# DB_MotherBoardConnectors.net
KiCad netlist of a schematic drawn in Altium Designer
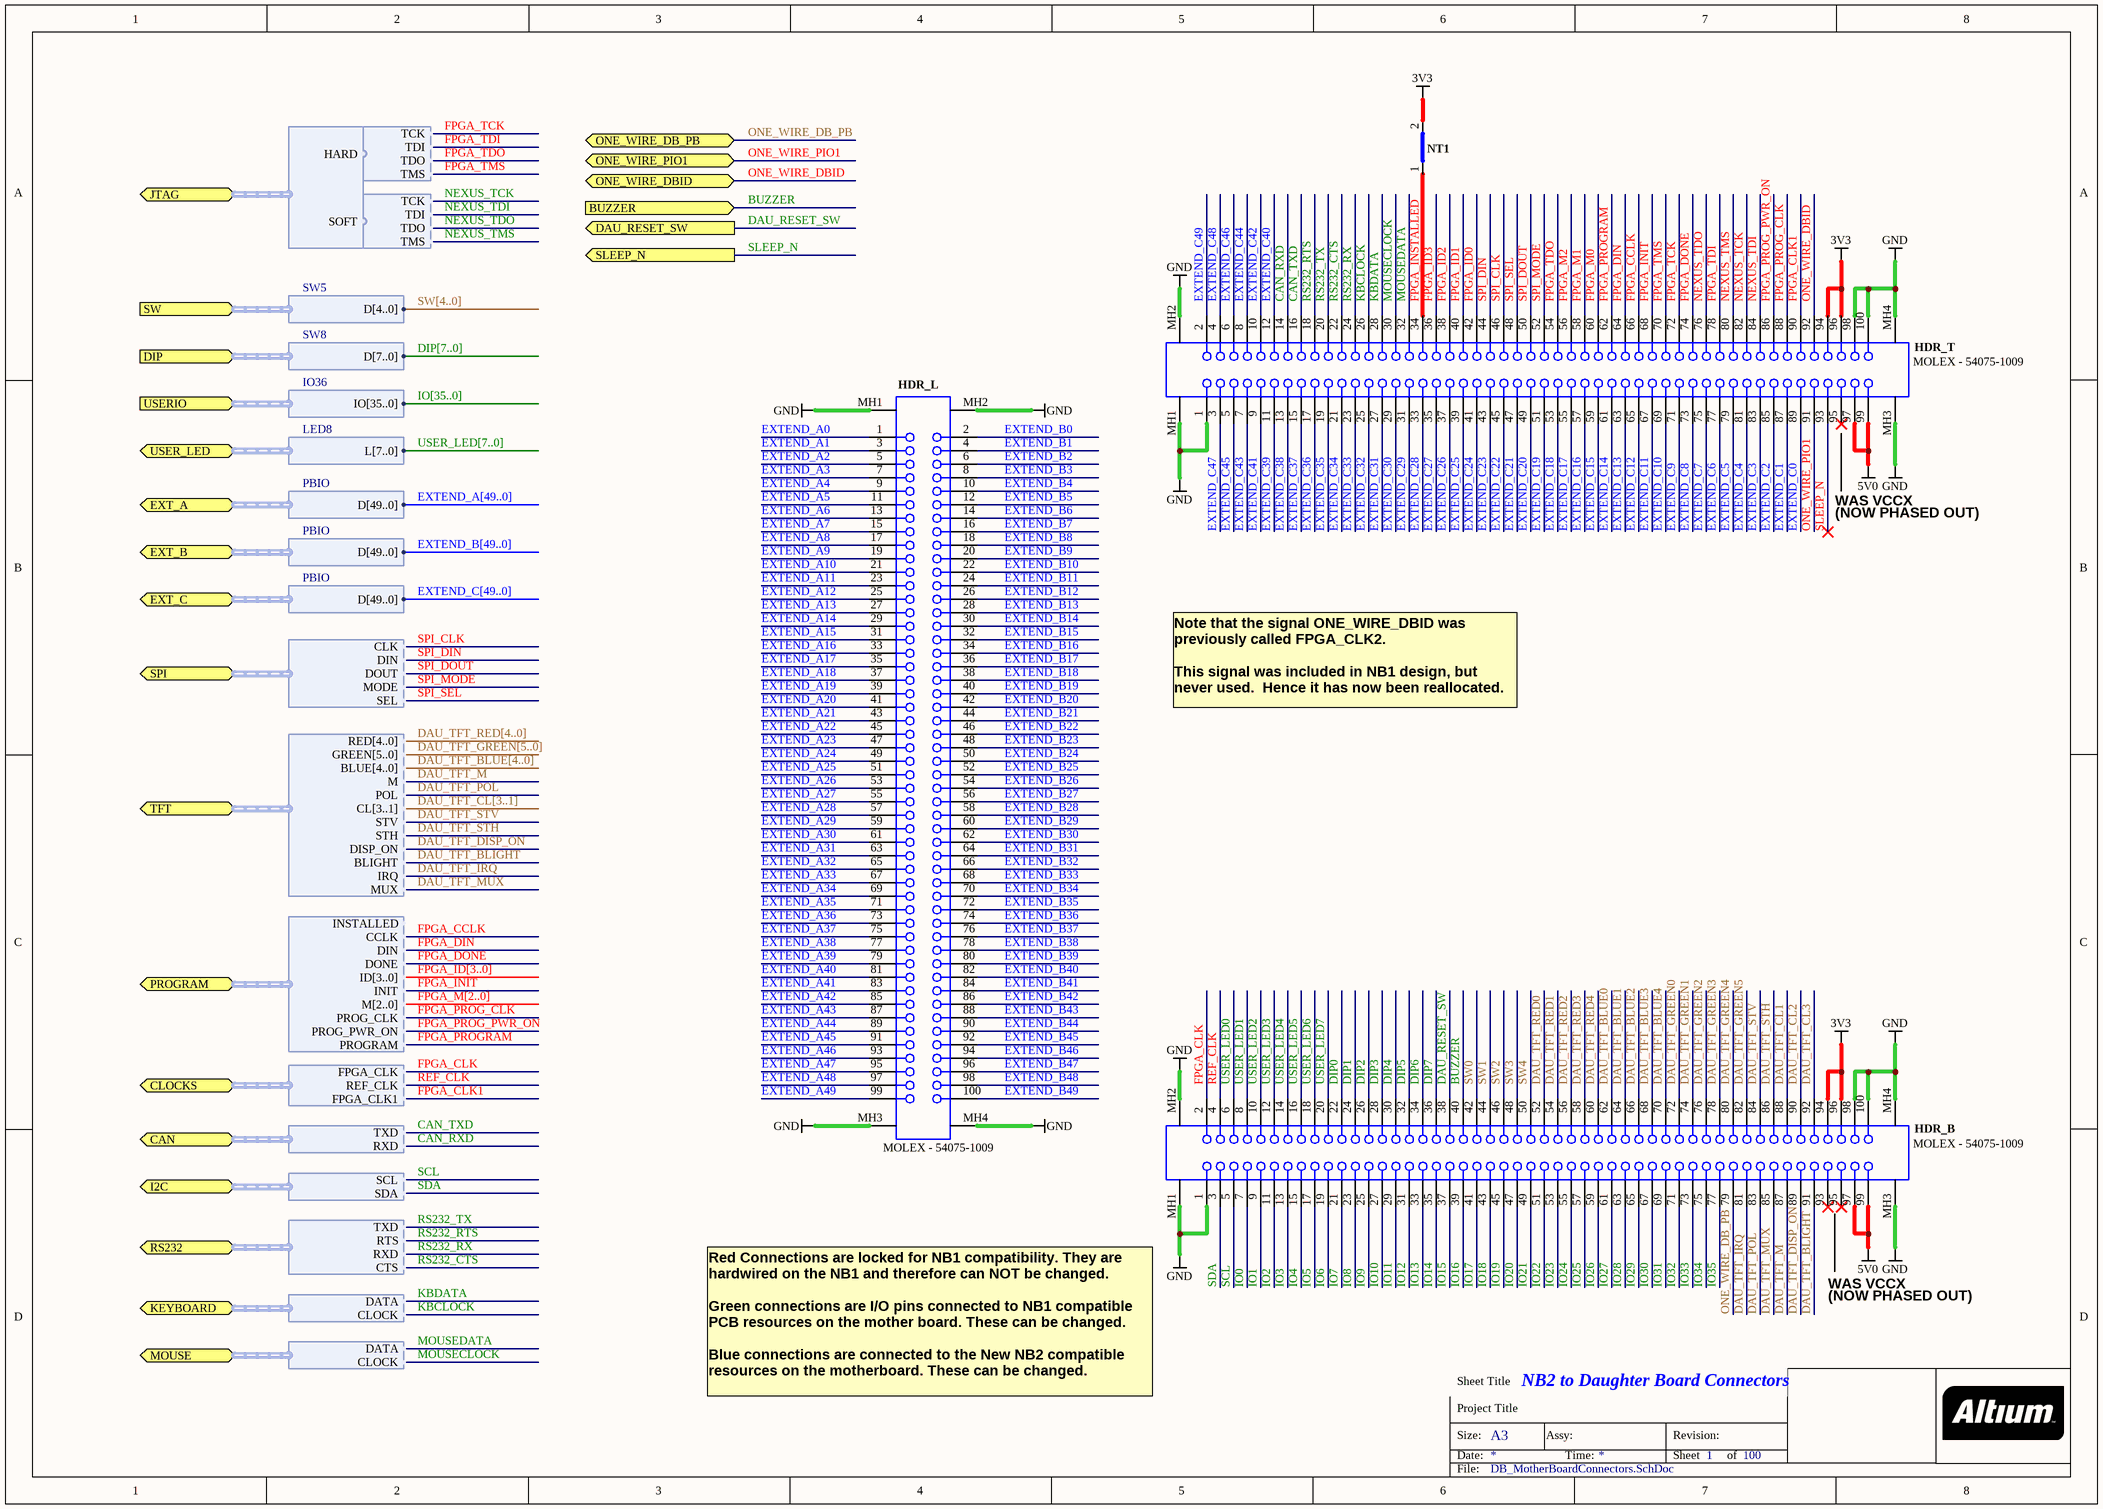
[diagram p0: DB_MotherBoardConnectors.SchDoc]

(export (version "E")
  (design (tool "Eeschema 10.0.6"))
  (components
    (comp (ref "HDR_B")
      (value "MOLEX - 54075-1009")
      (footprint "54075")
      (description "Connector, Molex Docking Station 100 Pin Male 54075")
      (libsource (lib "AltiumDesignLibrary") (part "CON-DOCKSTAT-100-M-STR"))
    )
    (comp (ref "HDR_L")
      (value "MOLEX - 54075-1009")
      (footprint "54075")
      (description "Connector, Molex Docking Station 100 Pin Male 54075")
      (libsource (lib "AltiumDesignLibrary") (part "CON-DOCKSTAT-100-M-STR"))
    )
    (comp (ref "HDR_T")
      (value "MOLEX - 54075-1009")
      (footprint "54075")
      (description "Connector, Molex Docking Station 100 Pin Male 54075")
      (libsource (lib "AltiumDesignLibrary") (part "CON-DOCKSTAT-100-M-STR"))
    )
    (comp (ref "NT1")
      (value "Net Tie SMT2")
      (footprint "NETTIE-SMT2-8X8")
      (description "Net-Tie, Surface Mount, 2 x 0.4mm x 0.2mm SMT Pads - For 0.2mm Track")
      (libsource (lib "AltiumDesignLibrary") (part "NETTIE-SMT2"))
    )
  )
  (nets
    (net (code "16") (name "/BUZZER") (class "Default")
      (node (ref "HDR_B") (pin "40") (pinfunction "40_40") (pintype "passive"))
    )
    (net (code "17") (name "/CAN_RXD") (class "Default")
      (node (ref "HDR_T") (pin "14") (pinfunction "14_14") (pintype "passive"))
    )
    (net (code "18") (name "/CAN_TXD") (class "Default")
      (node (ref "HDR_T") (pin "16") (pinfunction "16_16") (pintype "passive"))
    )
    (net (code "19") (name "/DAU_RESET_SW") (class "Default")
      (node (ref "HDR_B") (pin "38") (pinfunction "38_38") (pintype "passive"))
    )
    (net (code "20") (name "/DAU_TFT_BLIGHT") (class "Default")
      (node (ref "HDR_B") (pin "91") (pinfunction "91_91") (pintype "passive"))
    )
    (net (code "21") (name "/DAU_TFT_BLUE0") (class "Default")
      (node (ref "HDR_B") (pin "62") (pinfunction "62_62") (pintype "passive"))
    )
    (net (code "22") (name "/DAU_TFT_BLUE1") (class "Default")
      (node (ref "HDR_B") (pin "64") (pinfunction "64_64") (pintype "passive"))
    )
    (net (code "23") (name "/DAU_TFT_BLUE2") (class "Default")
      (node (ref "HDR_B") (pin "66") (pinfunction "66_66") (pintype "passive"))
    )
    (net (code "24") (name "/DAU_TFT_BLUE3") (class "Default")
      (node (ref "HDR_B") (pin "68") (pinfunction "68_68") (pintype "passive"))
    )
    (net (code "25") (name "/DAU_TFT_BLUE4") (class "Default")
      (node (ref "HDR_B") (pin "70") (pinfunction "70_70") (pintype "passive"))
    )
    (net (code "27") (name "/DAU_TFT_CL1") (class "Default")
      (node (ref "HDR_B") (pin "88") (pinfunction "88_88") (pintype "passive"))
    )
    (net (code "28") (name "/DAU_TFT_CL2") (class "Default")
      (node (ref "HDR_B") (pin "90") (pinfunction "90_90") (pintype "passive"))
    )
    (net (code "29") (name "/DAU_TFT_CL3") (class "Default")
      (node (ref "HDR_B") (pin "92") (pinfunction "92_92") (pintype "passive"))
    )
    (net (code "30") (name "/DAU_TFT_DISP_ON") (class "Default")
      (node (ref "HDR_B") (pin "89") (pinfunction "89_89") (pintype "passive"))
    )
    (net (code "31") (name "/DAU_TFT_GREEN0") (class "Default")
      (node (ref "HDR_B") (pin "72") (pinfunction "72_72") (pintype "passive"))
    )
    (net (code "32") (name "/DAU_TFT_GREEN1") (class "Default")
      (node (ref "HDR_B") (pin "74") (pinfunction "74_74") (pintype "passive"))
    )
    (net (code "33") (name "/DAU_TFT_GREEN2") (class "Default")
      (node (ref "HDR_B") (pin "76") (pinfunction "76_76") (pintype "passive"))
    )
    (net (code "34") (name "/DAU_TFT_GREEN3") (class "Default")
      (node (ref "HDR_B") (pin "78") (pinfunction "78_78") (pintype "passive"))
    )
    (net (code "35") (name "/DAU_TFT_GREEN4") (class "Default")
      (node (ref "HDR_B") (pin "80") (pinfunction "80_80") (pintype "passive"))
    )
    (net (code "36") (name "/DAU_TFT_GREEN5") (class "Default")
      (node (ref "HDR_B") (pin "82") (pinfunction "82_82") (pintype "passive"))
    )
    (net (code "38") (name "/DAU_TFT_IRQ") (class "Default")
      (node (ref "HDR_B") (pin "81") (pinfunction "81_81") (pintype "passive"))
    )
    (net (code "39") (name "/DAU_TFT_M") (class "Default")
      (node (ref "HDR_B") (pin "87") (pinfunction "87_87") (pintype "passive"))
    )
    (net (code "40") (name "/DAU_TFT_MUX") (class "Default")
      (node (ref "HDR_B") (pin "85") (pinfunction "85_85") (pintype "passive"))
    )
    (net (code "41") (name "/DAU_TFT_POL") (class "Default")
      (node (ref "HDR_B") (pin "83") (pinfunction "83_83") (pintype "passive"))
    )
    (net (code "42") (name "/DAU_TFT_RED0") (class "Default")
      (node (ref "HDR_B") (pin "52") (pinfunction "52_52") (pintype "passive"))
    )
    (net (code "43") (name "/DAU_TFT_RED1") (class "Default")
      (node (ref "HDR_B") (pin "54") (pinfunction "54_54") (pintype "passive"))
    )
    (net (code "44") (name "/DAU_TFT_RED2") (class "Default")
      (node (ref "HDR_B") (pin "56") (pinfunction "56_56") (pintype "passive"))
    )
    (net (code "45") (name "/DAU_TFT_RED3") (class "Default")
      (node (ref "HDR_B") (pin "58") (pinfunction "58_58") (pintype "passive"))
    )
    (net (code "46") (name "/DAU_TFT_RED4") (class "Default")
      (node (ref "HDR_B") (pin "60") (pinfunction "60_60") (pintype "passive"))
    )
    (net (code "48") (name "/DAU_TFT_STH") (class "Default")
      (node (ref "HDR_B") (pin "86") (pinfunction "86_86") (pintype "passive"))
    )
    (net (code "49") (name "/DAU_TFT_STV") (class "Default")
      (node (ref "HDR_B") (pin "84") (pinfunction "84_84") (pintype "passive"))
    )
    (net (code "50") (name "/DIP0") (class "Default")
      (node (ref "HDR_B") (pin "22") (pinfunction "22_22") (pintype "passive"))
    )
    (net (code "51") (name "/DIP1") (class "Default")
      (node (ref "HDR_B") (pin "24") (pinfunction "24_24") (pintype "passive"))
    )
    (net (code "52") (name "/DIP2") (class "Default")
      (node (ref "HDR_B") (pin "26") (pinfunction "26_26") (pintype "passive"))
    )
    (net (code "53") (name "/DIP3") (class "Default")
      (node (ref "HDR_B") (pin "28") (pinfunction "28_28") (pintype "passive"))
    )
    (net (code "54") (name "/DIP4") (class "Default")
      (node (ref "HDR_B") (pin "30") (pinfunction "30_30") (pintype "passive"))
    )
    (net (code "55") (name "/DIP5") (class "Default")
      (node (ref "HDR_B") (pin "32") (pinfunction "32_32") (pintype "passive"))
    )
    (net (code "56") (name "/DIP6") (class "Default")
      (node (ref "HDR_B") (pin "34") (pinfunction "34_34") (pintype "passive"))
    )
    (net (code "57") (name "/DIP7") (class "Default")
      (node (ref "HDR_B") (pin "36") (pinfunction "36_36") (pintype "passive"))
    )
    (net (code "59") (name "/EXTEND_A0") (class "Default")
      (node (ref "HDR_L") (pin "1") (pinfunction "1_1") (pintype "passive"))
    )
    (net (code "60") (name "/EXTEND_A1") (class "Default")
      (node (ref "HDR_L") (pin "3") (pinfunction "3_3") (pintype "passive"))
    )
    (net (code "61") (name "/EXTEND_A2") (class "Default")
      (node (ref "HDR_L") (pin "5") (pinfunction "5_5") (pintype "passive"))
    )
    (net (code "62") (name "/EXTEND_A3") (class "Default")
      (node (ref "HDR_L") (pin "7") (pinfunction "7_7") (pintype "passive"))
    )
    (net (code "63") (name "/EXTEND_A4") (class "Default")
      (node (ref "HDR_L") (pin "9") (pinfunction "9_9") (pintype "passive"))
    )
    (net (code "64") (name "/EXTEND_A5") (class "Default")
      (node (ref "HDR_L") (pin "11") (pinfunction "11_11") (pintype "passive"))
    )
    (net (code "65") (name "/EXTEND_A6") (class "Default")
      (node (ref "HDR_L") (pin "13") (pinfunction "13_13") (pintype "passive"))
    )
    (net (code "66") (name "/EXTEND_A7") (class "Default")
      (node (ref "HDR_L") (pin "15") (pinfunction "15_15") (pintype "passive"))
    )
    (net (code "67") (name "/EXTEND_A8") (class "Default")
      (node (ref "HDR_L") (pin "17") (pinfunction "17_17") (pintype "passive"))
    )
    (net (code "68") (name "/EXTEND_A9") (class "Default")
      (node (ref "HDR_L") (pin "19") (pinfunction "19_19") (pintype "passive"))
    )
    (net (code "69") (name "/EXTEND_A10") (class "Default")
      (node (ref "HDR_L") (pin "21") (pinfunction "21_21") (pintype "passive"))
    )
    (net (code "70") (name "/EXTEND_A11") (class "Default")
      (node (ref "HDR_L") (pin "23") (pinfunction "23_23") (pintype "passive"))
    )
    (net (code "71") (name "/EXTEND_A12") (class "Default")
      (node (ref "HDR_L") (pin "25") (pinfunction "25_25") (pintype "passive"))
    )
    (net (code "72") (name "/EXTEND_A13") (class "Default")
      (node (ref "HDR_L") (pin "27") (pinfunction "27_27") (pintype "passive"))
    )
    (net (code "73") (name "/EXTEND_A14") (class "Default")
      (node (ref "HDR_L") (pin "29") (pinfunction "29_29") (pintype "passive"))
    )
    (net (code "74") (name "/EXTEND_A15") (class "Default")
      (node (ref "HDR_L") (pin "31") (pinfunction "31_31") (pintype "passive"))
    )
    (net (code "75") (name "/EXTEND_A16") (class "Default")
      (node (ref "HDR_L") (pin "33") (pinfunction "33_33") (pintype "passive"))
    )
    (net (code "76") (name "/EXTEND_A17") (class "Default")
      (node (ref "HDR_L") (pin "35") (pinfunction "35_35") (pintype "passive"))
    )
    (net (code "77") (name "/EXTEND_A18") (class "Default")
      (node (ref "HDR_L") (pin "37") (pinfunction "37_37") (pintype "passive"))
    )
    (net (code "78") (name "/EXTEND_A19") (class "Default")
      (node (ref "HDR_L") (pin "39") (pinfunction "39_39") (pintype "passive"))
    )
    (net (code "79") (name "/EXTEND_A20") (class "Default")
      (node (ref "HDR_L") (pin "41") (pinfunction "41_41") (pintype "passive"))
    )
    (net (code "80") (name "/EXTEND_A21") (class "Default")
      (node (ref "HDR_L") (pin "43") (pinfunction "43_43") (pintype "passive"))
    )
    (net (code "81") (name "/EXTEND_A22") (class "Default")
      (node (ref "HDR_L") (pin "45") (pinfunction "45_45") (pintype "passive"))
    )
    (net (code "82") (name "/EXTEND_A23") (class "Default")
      (node (ref "HDR_L") (pin "47") (pinfunction "47_47") (pintype "passive"))
    )
    (net (code "83") (name "/EXTEND_A24") (class "Default")
      (node (ref "HDR_L") (pin "49") (pinfunction "49_49") (pintype "passive"))
    )
    (net (code "84") (name "/EXTEND_A25") (class "Default")
      (node (ref "HDR_L") (pin "51") (pinfunction "51_51") (pintype "passive"))
    )
    (net (code "85") (name "/EXTEND_A26") (class "Default")
      (node (ref "HDR_L") (pin "53") (pinfunction "53_53") (pintype "passive"))
    )
    (net (code "86") (name "/EXTEND_A27") (class "Default")
      (node (ref "HDR_L") (pin "55") (pinfunction "55_55") (pintype "passive"))
    )
    (net (code "87") (name "/EXTEND_A28") (class "Default")
      (node (ref "HDR_L") (pin "57") (pinfunction "57_57") (pintype "passive"))
    )
    (net (code "88") (name "/EXTEND_A29") (class "Default")
      (node (ref "HDR_L") (pin "59") (pinfunction "59_59") (pintype "passive"))
    )
    (net (code "89") (name "/EXTEND_A30") (class "Default")
      (node (ref "HDR_L") (pin "61") (pinfunction "61_61") (pintype "passive"))
    )
    (net (code "90") (name "/EXTEND_A31") (class "Default")
      (node (ref "HDR_L") (pin "63") (pinfunction "63_63") (pintype "passive"))
    )
    (net (code "91") (name "/EXTEND_A32") (class "Default")
      (node (ref "HDR_L") (pin "65") (pinfunction "65_65") (pintype "passive"))
    )
    (net (code "92") (name "/EXTEND_A33") (class "Default")
      (node (ref "HDR_L") (pin "67") (pinfunction "67_67") (pintype "passive"))
    )
    (net (code "93") (name "/EXTEND_A34") (class "Default")
      (node (ref "HDR_L") (pin "69") (pinfunction "69_69") (pintype "passive"))
    )
    (net (code "94") (name "/EXTEND_A35") (class "Default")
      (node (ref "HDR_L") (pin "71") (pinfunction "71_71") (pintype "passive"))
    )
    (net (code "95") (name "/EXTEND_A36") (class "Default")
      (node (ref "HDR_L") (pin "73") (pinfunction "73_73") (pintype "passive"))
    )
    (net (code "96") (name "/EXTEND_A37") (class "Default")
      (node (ref "HDR_L") (pin "75") (pinfunction "75_75") (pintype "passive"))
    )
    (net (code "97") (name "/EXTEND_A38") (class "Default")
      (node (ref "HDR_L") (pin "77") (pinfunction "77_77") (pintype "passive"))
    )
    (net (code "98") (name "/EXTEND_A39") (class "Default")
      (node (ref "HDR_L") (pin "79") (pinfunction "79_79") (pintype "passive"))
    )
    (net (code "99") (name "/EXTEND_A40") (class "Default")
      (node (ref "HDR_L") (pin "81") (pinfunction "81_81") (pintype "passive"))
    )
    (net (code "100") (name "/EXTEND_A41") (class "Default")
      (node (ref "HDR_L") (pin "83") (pinfunction "83_83") (pintype "passive"))
    )
    (net (code "101") (name "/EXTEND_A42") (class "Default")
      (node (ref "HDR_L") (pin "85") (pinfunction "85_85") (pintype "passive"))
    )
    (net (code "102") (name "/EXTEND_A43") (class "Default")
      (node (ref "HDR_L") (pin "87") (pinfunction "87_87") (pintype "passive"))
    )
    (net (code "103") (name "/EXTEND_A44") (class "Default")
      (node (ref "HDR_L") (pin "89") (pinfunction "89_89") (pintype "passive"))
    )
    (net (code "104") (name "/EXTEND_A45") (class "Default")
      (node (ref "HDR_L") (pin "91") (pinfunction "91_91") (pintype "passive"))
    )
    (net (code "105") (name "/EXTEND_A46") (class "Default")
      (node (ref "HDR_L") (pin "93") (pinfunction "93_93") (pintype "passive"))
    )
    (net (code "106") (name "/EXTEND_A47") (class "Default")
      (node (ref "HDR_L") (pin "95") (pinfunction "95_95") (pintype "passive"))
    )
    (net (code "107") (name "/EXTEND_A48") (class "Default")
      (node (ref "HDR_L") (pin "97") (pinfunction "97_97") (pintype "passive"))
    )
    (net (code "108") (name "/EXTEND_A49") (class "Default")
      (node (ref "HDR_L") (pin "99") (pinfunction "99_99") (pintype "passive"))
    )
    (net (code "110") (name "/EXTEND_B0") (class "Default")
      (node (ref "HDR_L") (pin "2") (pinfunction "2_2") (pintype "passive"))
    )
    (net (code "111") (name "/EXTEND_B1") (class "Default")
      (node (ref "HDR_L") (pin "4") (pinfunction "4_4") (pintype "passive"))
    )
    (net (code "112") (name "/EXTEND_B2") (class "Default")
      (node (ref "HDR_L") (pin "6") (pinfunction "6_6") (pintype "passive"))
    )
    (net (code "113") (name "/EXTEND_B3") (class "Default")
      (node (ref "HDR_L") (pin "8") (pinfunction "8_8") (pintype "passive"))
    )
    (net (code "114") (name "/EXTEND_B4") (class "Default")
      (node (ref "HDR_L") (pin "10") (pinfunction "10_10") (pintype "passive"))
    )
    (net (code "115") (name "/EXTEND_B5") (class "Default")
      (node (ref "HDR_L") (pin "12") (pinfunction "12_12") (pintype "passive"))
    )
    (net (code "116") (name "/EXTEND_B6") (class "Default")
      (node (ref "HDR_L") (pin "14") (pinfunction "14_14") (pintype "passive"))
    )
    (net (code "117") (name "/EXTEND_B7") (class "Default")
      (node (ref "HDR_L") (pin "16") (pinfunction "16_16") (pintype "passive"))
    )
    (net (code "118") (name "/EXTEND_B8") (class "Default")
      (node (ref "HDR_L") (pin "18") (pinfunction "18_18") (pintype "passive"))
    )
    (net (code "119") (name "/EXTEND_B9") (class "Default")
      (node (ref "HDR_L") (pin "20") (pinfunction "20_20") (pintype "passive"))
    )
    (net (code "120") (name "/EXTEND_B10") (class "Default")
      (node (ref "HDR_L") (pin "22") (pinfunction "22_22") (pintype "passive"))
    )
    (net (code "121") (name "/EXTEND_B11") (class "Default")
      (node (ref "HDR_L") (pin "24") (pinfunction "24_24") (pintype "passive"))
    )
    (net (code "122") (name "/EXTEND_B12") (class "Default")
      (node (ref "HDR_L") (pin "26") (pinfunction "26_26") (pintype "passive"))
    )
    (net (code "123") (name "/EXTEND_B13") (class "Default")
      (node (ref "HDR_L") (pin "28") (pinfunction "28_28") (pintype "passive"))
    )
    (net (code "124") (name "/EXTEND_B14") (class "Default")
      (node (ref "HDR_L") (pin "30") (pinfunction "30_30") (pintype "passive"))
    )
    (net (code "125") (name "/EXTEND_B15") (class "Default")
      (node (ref "HDR_L") (pin "32") (pinfunction "32_32") (pintype "passive"))
    )
    (net (code "126") (name "/EXTEND_B16") (class "Default")
      (node (ref "HDR_L") (pin "34") (pinfunction "34_34") (pintype "passive"))
    )
    (net (code "127") (name "/EXTEND_B17") (class "Default")
      (node (ref "HDR_L") (pin "36") (pinfunction "36_36") (pintype "passive"))
    )
    (net (code "128") (name "/EXTEND_B18") (class "Default")
      (node (ref "HDR_L") (pin "38") (pinfunction "38_38") (pintype "passive"))
    )
    (net (code "129") (name "/EXTEND_B19") (class "Default")
      (node (ref "HDR_L") (pin "40") (pinfunction "40_40") (pintype "passive"))
    )
    (net (code "130") (name "/EXTEND_B20") (class "Default")
      (node (ref "HDR_L") (pin "42") (pinfunction "42_42") (pintype "passive"))
    )
    (net (code "131") (name "/EXTEND_B21") (class "Default")
      (node (ref "HDR_L") (pin "44") (pinfunction "44_44") (pintype "passive"))
    )
    (net (code "132") (name "/EXTEND_B22") (class "Default")
      (node (ref "HDR_L") (pin "46") (pinfunction "46_46") (pintype "passive"))
    )
    (net (code "133") (name "/EXTEND_B23") (class "Default")
      (node (ref "HDR_L") (pin "48") (pinfunction "48_48") (pintype "passive"))
    )
    (net (code "134") (name "/EXTEND_B24") (class "Default")
      (node (ref "HDR_L") (pin "50") (pinfunction "50_50") (pintype "passive"))
    )
    (net (code "135") (name "/EXTEND_B25") (class "Default")
      (node (ref "HDR_L") (pin "52") (pinfunction "52_52") (pintype "passive"))
    )
    (net (code "136") (name "/EXTEND_B26") (class "Default")
      (node (ref "HDR_L") (pin "54") (pinfunction "54_54") (pintype "passive"))
    )
    (net (code "137") (name "/EXTEND_B27") (class "Default")
      (node (ref "HDR_L") (pin "56") (pinfunction "56_56") (pintype "passive"))
    )
    (net (code "138") (name "/EXTEND_B28") (class "Default")
      (node (ref "HDR_L") (pin "58") (pinfunction "58_58") (pintype "passive"))
    )
    (net (code "139") (name "/EXTEND_B29") (class "Default")
      (node (ref "HDR_L") (pin "60") (pinfunction "60_60") (pintype "passive"))
    )
    (net (code "140") (name "/EXTEND_B30") (class "Default")
      (node (ref "HDR_L") (pin "62") (pinfunction "62_62") (pintype "passive"))
    )
    (net (code "141") (name "/EXTEND_B31") (class "Default")
      (node (ref "HDR_L") (pin "64") (pinfunction "64_64") (pintype "passive"))
    )
    (net (code "142") (name "/EXTEND_B32") (class "Default")
      (node (ref "HDR_L") (pin "66") (pinfunction "66_66") (pintype "passive"))
    )
    (net (code "143") (name "/EXTEND_B33") (class "Default")
      (node (ref "HDR_L") (pin "68") (pinfunction "68_68") (pintype "passive"))
    )
    (net (code "144") (name "/EXTEND_B34") (class "Default")
      (node (ref "HDR_L") (pin "70") (pinfunction "70_70") (pintype "passive"))
    )
    (net (code "145") (name "/EXTEND_B35") (class "Default")
      (node (ref "HDR_L") (pin "72") (pinfunction "72_72") (pintype "passive"))
    )
    (net (code "146") (name "/EXTEND_B36") (class "Default")
      (node (ref "HDR_L") (pin "74") (pinfunction "74_74") (pintype "passive"))
    )
    (net (code "147") (name "/EXTEND_B37") (class "Default")
      (node (ref "HDR_L") (pin "76") (pinfunction "76_76") (pintype "passive"))
    )
    (net (code "148") (name "/EXTEND_B38") (class "Default")
      (node (ref "HDR_L") (pin "78") (pinfunction "78_78") (pintype "passive"))
    )
    (net (code "149") (name "/EXTEND_B39") (class "Default")
      (node (ref "HDR_L") (pin "80") (pinfunction "80_80") (pintype "passive"))
    )
    (net (code "150") (name "/EXTEND_B40") (class "Default")
      (node (ref "HDR_L") (pin "82") (pinfunction "82_82") (pintype "passive"))
    )
    (net (code "151") (name "/EXTEND_B41") (class "Default")
      (node (ref "HDR_L") (pin "84") (pinfunction "84_84") (pintype "passive"))
    )
    (net (code "152") (name "/EXTEND_B42") (class "Default")
      (node (ref "HDR_L") (pin "86") (pinfunction "86_86") (pintype "passive"))
    )
    (net (code "153") (name "/EXTEND_B43") (class "Default")
      (node (ref "HDR_L") (pin "88") (pinfunction "88_88") (pintype "passive"))
    )
    (net (code "154") (name "/EXTEND_B44") (class "Default")
      (node (ref "HDR_L") (pin "90") (pinfunction "90_90") (pintype "passive"))
    )
    (net (code "155") (name "/EXTEND_B45") (class "Default")
      (node (ref "HDR_L") (pin "92") (pinfunction "92_92") (pintype "passive"))
    )
    (net (code "156") (name "/EXTEND_B46") (class "Default")
      (node (ref "HDR_L") (pin "94") (pinfunction "94_94") (pintype "passive"))
    )
    (net (code "157") (name "/EXTEND_B47") (class "Default")
      (node (ref "HDR_L") (pin "96") (pinfunction "96_96") (pintype "passive"))
    )
    (net (code "158") (name "/EXTEND_B48") (class "Default")
      (node (ref "HDR_L") (pin "98") (pinfunction "98_98") (pintype "passive"))
    )
    (net (code "159") (name "/EXTEND_B49") (class "Default")
      (node (ref "HDR_L") (pin "100") (pinfunction "100_100") (pintype "passive"))
    )
    (net (code "161") (name "/EXTEND_C0") (class "Default")
      (node (ref "HDR_T") (pin "89") (pinfunction "89_89") (pintype "passive"))
    )
    (net (code "162") (name "/EXTEND_C1") (class "Default")
      (node (ref "HDR_T") (pin "87") (pinfunction "87_87") (pintype "passive"))
    )
    (net (code "163") (name "/EXTEND_C2") (class "Default")
      (node (ref "HDR_T") (pin "85") (pinfunction "85_85") (pintype "passive"))
    )
    (net (code "164") (name "/EXTEND_C3") (class "Default")
      (node (ref "HDR_T") (pin "83") (pinfunction "83_83") (pintype "passive"))
    )
    (net (code "165") (name "/EXTEND_C4") (class "Default")
      (node (ref "HDR_T") (pin "81") (pinfunction "81_81") (pintype "passive"))
    )
    (net (code "166") (name "/EXTEND_C5") (class "Default")
      (node (ref "HDR_T") (pin "79") (pinfunction "79_79") (pintype "passive"))
    )
    (net (code "167") (name "/EXTEND_C6") (class "Default")
      (node (ref "HDR_T") (pin "77") (pinfunction "77_77") (pintype "passive"))
    )
    (net (code "168") (name "/EXTEND_C7") (class "Default")
      (node (ref "HDR_T") (pin "75") (pinfunction "75_75") (pintype "passive"))
    )
    (net (code "169") (name "/EXTEND_C8") (class "Default")
      (node (ref "HDR_T") (pin "73") (pinfunction "73_73") (pintype "passive"))
    )
    (net (code "170") (name "/EXTEND_C9") (class "Default")
      (node (ref "HDR_T") (pin "71") (pinfunction "71_71") (pintype "passive"))
    )
    (net (code "171") (name "/EXTEND_C10") (class "Default")
      (node (ref "HDR_T") (pin "69") (pinfunction "69_69") (pintype "passive"))
    )
    (net (code "172") (name "/EXTEND_C11") (class "Default")
      (node (ref "HDR_T") (pin "67") (pinfunction "67_67") (pintype "passive"))
    )
    (net (code "173") (name "/EXTEND_C12") (class "Default")
      (node (ref "HDR_T") (pin "65") (pinfunction "65_65") (pintype "passive"))
    )
    (net (code "174") (name "/EXTEND_C13") (class "Default")
      (node (ref "HDR_T") (pin "63") (pinfunction "63_63") (pintype "passive"))
    )
    (net (code "175") (name "/EXTEND_C14") (class "Default")
      (node (ref "HDR_T") (pin "61") (pinfunction "61_61") (pintype "passive"))
    )
    (net (code "176") (name "/EXTEND_C15") (class "Default")
      (node (ref "HDR_T") (pin "59") (pinfunction "59_59") (pintype "passive"))
    )
    (net (code "177") (name "/EXTEND_C16") (class "Default")
      (node (ref "HDR_T") (pin "57") (pinfunction "57_57") (pintype "passive"))
    )
    (net (code "178") (name "/EXTEND_C17") (class "Default")
      (node (ref "HDR_T") (pin "55") (pinfunction "55_55") (pintype "passive"))
    )
    (net (code "179") (name "/EXTEND_C18") (class "Default")
      (node (ref "HDR_T") (pin "53") (pinfunction "53_53") (pintype "passive"))
    )
    (net (code "180") (name "/EXTEND_C19") (class "Default")
      (node (ref "HDR_T") (pin "51") (pinfunction "51_51") (pintype "passive"))
    )
    (net (code "181") (name "/EXTEND_C20") (class "Default")
      (node (ref "HDR_T") (pin "49") (pinfunction "49_49") (pintype "passive"))
    )
    (net (code "182") (name "/EXTEND_C21") (class "Default")
      (node (ref "HDR_T") (pin "47") (pinfunction "47_47") (pintype "passive"))
    )
    (net (code "183") (name "/EXTEND_C22") (class "Default")
      (node (ref "HDR_T") (pin "45") (pinfunction "45_45") (pintype "passive"))
    )
    (net (code "184") (name "/EXTEND_C23") (class "Default")
      (node (ref "HDR_T") (pin "43") (pinfunction "43_43") (pintype "passive"))
    )
    (net (code "185") (name "/EXTEND_C24") (class "Default")
      (node (ref "HDR_T") (pin "41") (pinfunction "41_41") (pintype "passive"))
    )
    (net (code "186") (name "/EXTEND_C25") (class "Default")
      (node (ref "HDR_T") (pin "39") (pinfunction "39_39") (pintype "passive"))
    )
    (net (code "187") (name "/EXTEND_C26") (class "Default")
      (node (ref "HDR_T") (pin "37") (pinfunction "37_37") (pintype "passive"))
    )
    (net (code "188") (name "/EXTEND_C27") (class "Default")
      (node (ref "HDR_T") (pin "35") (pinfunction "35_35") (pintype "passive"))
    )
    (net (code "189") (name "/EXTEND_C28") (class "Default")
      (node (ref "HDR_T") (pin "33") (pinfunction "33_33") (pintype "passive"))
    )
    (net (code "190") (name "/EXTEND_C29") (class "Default")
      (node (ref "HDR_T") (pin "31") (pinfunction "31_31") (pintype "passive"))
    )
    (net (code "191") (name "/EXTEND_C30") (class "Default")
      (node (ref "HDR_T") (pin "29") (pinfunction "29_29") (pintype "passive"))
    )
    (net (code "192") (name "/EXTEND_C31") (class "Default")
      (node (ref "HDR_T") (pin "27") (pinfunction "27_27") (pintype "passive"))
    )
    (net (code "193") (name "/EXTEND_C32") (class "Default")
      (node (ref "HDR_T") (pin "25") (pinfunction "25_25") (pintype "passive"))
    )
    (net (code "194") (name "/EXTEND_C33") (class "Default")
      (node (ref "HDR_T") (pin "23") (pinfunction "23_23") (pintype "passive"))
    )
    (net (code "195") (name "/EXTEND_C34") (class "Default")
      (node (ref "HDR_T") (pin "21") (pinfunction "21_21") (pintype "passive"))
    )
    (net (code "196") (name "/EXTEND_C35") (class "Default")
      (node (ref "HDR_T") (pin "19") (pinfunction "19_19") (pintype "passive"))
    )
    (net (code "197") (name "/EXTEND_C36") (class "Default")
      (node (ref "HDR_T") (pin "17") (pinfunction "17_17") (pintype "passive"))
    )
    (net (code "198") (name "/EXTEND_C37") (class "Default")
      (node (ref "HDR_T") (pin "15") (pinfunction "15_15") (pintype "passive"))
    )
    (net (code "199") (name "/EXTEND_C38") (class "Default")
      (node (ref "HDR_T") (pin "13") (pinfunction "13_13") (pintype "passive"))
    )
    (net (code "200") (name "/EXTEND_C39") (class "Default")
      (node (ref "HDR_T") (pin "11") (pinfunction "11_11") (pintype "passive"))
    )
    (net (code "201") (name "/EXTEND_C40") (class "Default")
      (node (ref "HDR_T") (pin "12") (pinfunction "12_12") (pintype "passive"))
    )
    (net (code "202") (name "/EXTEND_C41") (class "Default")
      (node (ref "HDR_T") (pin "9") (pinfunction "9_9") (pintype "passive"))
    )
    (net (code "203") (name "/EXTEND_C42") (class "Default")
      (node (ref "HDR_T") (pin "10") (pinfunction "10_10") (pintype "passive"))
    )
    (net (code "204") (name "/EXTEND_C43") (class "Default")
      (node (ref "HDR_T") (pin "7") (pinfunction "7_7") (pintype "passive"))
    )
    (net (code "205") (name "/EXTEND_C44") (class "Default")
      (node (ref "HDR_T") (pin "8") (pinfunction "8_8") (pintype "passive"))
    )
    (net (code "206") (name "/EXTEND_C45") (class "Default")
      (node (ref "HDR_T") (pin "5") (pinfunction "5_5") (pintype "passive"))
    )
    (net (code "207") (name "/EXTEND_C46") (class "Default")
      (node (ref "HDR_T") (pin "6") (pinfunction "6_6") (pintype "passive"))
    )
    (net (code "208") (name "/EXTEND_C47") (class "Default")
      (node (ref "HDR_T") (pin "3") (pinfunction "3_3") (pintype "passive"))
    )
    (net (code "209") (name "/EXTEND_C48") (class "Default")
      (node (ref "HDR_T") (pin "4") (pinfunction "4_4") (pintype "passive"))
    )
    (net (code "210") (name "/EXTEND_C49") (class "Default")
      (node (ref "HDR_T") (pin "2") (pinfunction "2_2") (pintype "passive"))
    )
    (net (code "212") (name "/FPGA_CCLK") (class "Default")
      (node (ref "HDR_T") (pin "66") (pinfunction "66_66") (pintype "passive"))
    )
    (net (code "213") (name "/FPGA_CLK") (class "Default")
      (node (ref "HDR_B") (pin "2") (pinfunction "2_2") (pintype "passive"))
    )
    (net (code "214") (name "/FPGA_CLK1") (class "Default")
      (node (ref "HDR_T") (pin "90") (pinfunction "90_90") (pintype "passive"))
    )
    (net (code "215") (name "/FPGA_DIN") (class "Default")
      (node (ref "HDR_T") (pin "64") (pinfunction "64_64") (pintype "passive"))
    )
    (net (code "216") (name "/FPGA_DONE") (class "Default")
      (node (ref "HDR_T") (pin "74") (pinfunction "74_74") (pintype "passive"))
    )
    (net (code "217") (name "/FPGA_ID0") (class "Default")
      (node (ref "HDR_T") (pin "42") (pinfunction "42_42") (pintype "passive"))
    )
    (net (code "218") (name "/FPGA_ID1") (class "Default")
      (node (ref "HDR_T") (pin "40") (pinfunction "40_40") (pintype "passive"))
    )
    (net (code "219") (name "/FPGA_ID2") (class "Default")
      (node (ref "HDR_T") (pin "38") (pinfunction "38_38") (pintype "passive"))
    )
    (net (code "220") (name "/FPGA_ID3") (class "Default")
      (node (ref "HDR_T") (pin "36") (pinfunction "36_36") (pintype "passive"))
    )
    (net (code "222") (name "/FPGA_INIT") (class "Default")
      (node (ref "HDR_T") (pin "68") (pinfunction "68_68") (pintype "passive"))
    )
    (net (code "223") (name "/FPGA_INSTALLED") (class "Default")
      (node (ref "HDR_T") (pin "34") (pinfunction "34_34") (pintype "passive"))
      (node (ref "NT1") (pin "1") (pinfunction "Net1_1") (pintype "passive"))
    )
    (net (code "224") (name "/FPGA_M0") (class "Default")
      (node (ref "HDR_T") (pin "60") (pinfunction "60_60") (pintype "passive"))
    )
    (net (code "225") (name "/FPGA_M1") (class "Default")
      (node (ref "HDR_T") (pin "58") (pinfunction "58_58") (pintype "passive"))
    )
    (net (code "226") (name "/FPGA_M2") (class "Default")
      (node (ref "HDR_T") (pin "56") (pinfunction "56_56") (pintype "passive"))
    )
    (net (code "227") (name "/FPGA_PROGRAM") (class "Default")
      (node (ref "HDR_T") (pin "62") (pinfunction "62_62") (pintype "passive"))
    )
    (net (code "228") (name "/FPGA_PROG_CLK") (class "Default")
      (node (ref "HDR_T") (pin "88") (pinfunction "88_88") (pintype "passive"))
    )
    (net (code "229") (name "/FPGA_PROG_PWR_ON") (class "Default")
      (node (ref "HDR_T") (pin "86") (pinfunction "86_86") (pintype "passive"))
    )
    (net (code "230") (name "/FPGA_TCK") (class "Default")
      (node (ref "HDR_T") (pin "72") (pinfunction "72_72") (pintype "passive"))
    )
    (net (code "231") (name "/FPGA_TDI") (class "Default")
      (node (ref "HDR_T") (pin "78") (pinfunction "78_78") (pintype "passive"))
    )
    (net (code "232") (name "/FPGA_TDO") (class "Default")
      (node (ref "HDR_T") (pin "54") (pinfunction "54_54") (pintype "passive"))
    )
    (net (code "233") (name "/FPGA_TMS") (class "Default")
      (node (ref "HDR_T") (pin "70") (pinfunction "70_70") (pintype "passive"))
    )
    (net (code "234") (name "/IO0") (class "Default")
      (node (ref "HDR_B") (pin "7") (pinfunction "7_7") (pintype "passive"))
    )
    (net (code "235") (name "/IO1") (class "Default")
      (node (ref "HDR_B") (pin "9") (pinfunction "9_9") (pintype "passive"))
    )
    (net (code "236") (name "/IO2") (class "Default")
      (node (ref "HDR_B") (pin "11") (pinfunction "11_11") (pintype "passive"))
    )
    (net (code "237") (name "/IO3") (class "Default")
      (node (ref "HDR_B") (pin "13") (pinfunction "13_13") (pintype "passive"))
    )
    (net (code "238") (name "/IO4") (class "Default")
      (node (ref "HDR_B") (pin "15") (pinfunction "15_15") (pintype "passive"))
    )
    (net (code "239") (name "/IO5") (class "Default")
      (node (ref "HDR_B") (pin "17") (pinfunction "17_17") (pintype "passive"))
    )
    (net (code "240") (name "/IO6") (class "Default")
      (node (ref "HDR_B") (pin "19") (pinfunction "19_19") (pintype "passive"))
    )
    (net (code "241") (name "/IO7") (class "Default")
      (node (ref "HDR_B") (pin "21") (pinfunction "21_21") (pintype "passive"))
    )
    (net (code "242") (name "/IO8") (class "Default")
      (node (ref "HDR_B") (pin "23") (pinfunction "23_23") (pintype "passive"))
    )
    (net (code "243") (name "/IO9") (class "Default")
      (node (ref "HDR_B") (pin "25") (pinfunction "25_25") (pintype "passive"))
    )
    (net (code "244") (name "/IO10") (class "Default")
      (node (ref "HDR_B") (pin "27") (pinfunction "27_27") (pintype "passive"))
    )
    (net (code "245") (name "/IO11") (class "Default")
      (node (ref "HDR_B") (pin "29") (pinfunction "29_29") (pintype "passive"))
    )
    (net (code "246") (name "/IO12") (class "Default")
      (node (ref "HDR_B") (pin "31") (pinfunction "31_31") (pintype "passive"))
    )
    (net (code "247") (name "/IO13") (class "Default")
      (node (ref "HDR_B") (pin "33") (pinfunction "33_33") (pintype "passive"))
    )
    (net (code "248") (name "/IO14") (class "Default")
      (node (ref "HDR_B") (pin "35") (pinfunction "35_35") (pintype "passive"))
    )
    (net (code "249") (name "/IO15") (class "Default")
      (node (ref "HDR_B") (pin "37") (pinfunction "37_37") (pintype "passive"))
    )
    (net (code "250") (name "/IO16") (class "Default")
      (node (ref "HDR_B") (pin "39") (pinfunction "39_39") (pintype "passive"))
    )
    (net (code "251") (name "/IO17") (class "Default")
      (node (ref "HDR_B") (pin "41") (pinfunction "41_41") (pintype "passive"))
    )
    (net (code "252") (name "/IO18") (class "Default")
      (node (ref "HDR_B") (pin "43") (pinfunction "43_43") (pintype "passive"))
    )
    (net (code "253") (name "/IO19") (class "Default")
      (node (ref "HDR_B") (pin "45") (pinfunction "45_45") (pintype "passive"))
    )
    (net (code "254") (name "/IO20") (class "Default")
      (node (ref "HDR_B") (pin "47") (pinfunction "47_47") (pintype "passive"))
    )
    (net (code "255") (name "/IO21") (class "Default")
      (node (ref "HDR_B") (pin "49") (pinfunction "49_49") (pintype "passive"))
    )
    (net (code "256") (name "/IO22") (class "Default")
      (node (ref "HDR_B") (pin "51") (pinfunction "51_51") (pintype "passive"))
    )
    (net (code "257") (name "/IO23") (class "Default")
      (node (ref "HDR_B") (pin "53") (pinfunction "53_53") (pintype "passive"))
    )
    (net (code "258") (name "/IO24") (class "Default")
      (node (ref "HDR_B") (pin "55") (pinfunction "55_55") (pintype "passive"))
    )
    (net (code "259") (name "/IO25") (class "Default")
      (node (ref "HDR_B") (pin "57") (pinfunction "57_57") (pintype "passive"))
    )
    (net (code "260") (name "/IO26") (class "Default")
      (node (ref "HDR_B") (pin "59") (pinfunction "59_59") (pintype "passive"))
    )
    (net (code "261") (name "/IO27") (class "Default")
      (node (ref "HDR_B") (pin "61") (pinfunction "61_61") (pintype "passive"))
    )
    (net (code "262") (name "/IO28") (class "Default")
      (node (ref "HDR_B") (pin "63") (pinfunction "63_63") (pintype "passive"))
    )
    (net (code "263") (name "/IO29") (class "Default")
      (node (ref "HDR_B") (pin "65") (pinfunction "65_65") (pintype "passive"))
    )
    (net (code "264") (name "/IO30") (class "Default")
      (node (ref "HDR_B") (pin "67") (pinfunction "67_67") (pintype "passive"))
    )
    (net (code "265") (name "/IO31") (class "Default")
      (node (ref "HDR_B") (pin "69") (pinfunction "69_69") (pintype "passive"))
    )
    (net (code "266") (name "/IO32") (class "Default")
      (node (ref "HDR_B") (pin "71") (pinfunction "71_71") (pintype "passive"))
    )
    (net (code "267") (name "/IO33") (class "Default")
      (node (ref "HDR_B") (pin "73") (pinfunction "73_73") (pintype "passive"))
    )
    (net (code "268") (name "/IO34") (class "Default")
      (node (ref "HDR_B") (pin "75") (pinfunction "75_75") (pintype "passive"))
    )
    (net (code "269") (name "/IO35") (class "Default")
      (node (ref "HDR_B") (pin "77") (pinfunction "77_77") (pintype "passive"))
    )
    (net (code "271") (name "/KBCLOCK") (class "Default")
      (node (ref "HDR_T") (pin "26") (pinfunction "26_26") (pintype "passive"))
    )
    (net (code "272") (name "/KBDATA") (class "Default")
      (node (ref "HDR_T") (pin "28") (pinfunction "28_28") (pintype "passive"))
    )
    (net (code "273") (name "/MOUSECLOCK") (class "Default")
      (node (ref "HDR_T") (pin "30") (pinfunction "30_30") (pintype "passive"))
    )
    (net (code "274") (name "/MOUSEDATA") (class "Default")
      (node (ref "HDR_T") (pin "32") (pinfunction "32_32") (pintype "passive"))
    )
    (net (code "275") (name "/NEXUS_TCK") (class "Default")
      (node (ref "HDR_T") (pin "82") (pinfunction "82_82") (pintype "passive"))
    )
    (net (code "276") (name "/NEXUS_TDI") (class "Default")
      (node (ref "HDR_T") (pin "84") (pinfunction "84_84") (pintype "passive"))
    )
    (net (code "277") (name "/NEXUS_TDO") (class "Default")
      (node (ref "HDR_T") (pin "76") (pinfunction "76_76") (pintype "passive"))
    )
    (net (code "278") (name "/NEXUS_TMS") (class "Default")
      (node (ref "HDR_T") (pin "80") (pinfunction "80_80") (pintype "passive"))
    )
    (net (code "279") (name "/ONE_WIRE_DBID") (class "Default")
      (node (ref "HDR_T") (pin "92") (pinfunction "92_92") (pintype "passive"))
    )
    (net (code "280") (name "/ONE_WIRE_DB_PB") (class "Default")
      (node (ref "HDR_B") (pin "79") (pinfunction "79_79") (pintype "passive"))
    )
    (net (code "281") (name "/ONE_WIRE_PIO1") (class "Default")
      (node (ref "HDR_T") (pin "91") (pinfunction "91_91") (pintype "passive"))
    )
    (net (code "283") (name "/REF_CLK") (class "Default")
      (node (ref "HDR_B") (pin "4") (pinfunction "4_4") (pintype "passive"))
    )
    (net (code "284") (name "/RS232_CTS") (class "Default")
      (node (ref "HDR_T") (pin "22") (pinfunction "22_22") (pintype "passive"))
    )
    (net (code "285") (name "/RS232_RTS") (class "Default")
      (node (ref "HDR_T") (pin "18") (pinfunction "18_18") (pintype "passive"))
    )
    (net (code "286") (name "/RS232_RX") (class "Default")
      (node (ref "HDR_T") (pin "24") (pinfunction "24_24") (pintype "passive"))
    )
    (net (code "287") (name "/RS232_TX") (class "Default")
      (node (ref "HDR_T") (pin "20") (pinfunction "20_20") (pintype "passive"))
    )
    (net (code "288") (name "/SCL") (class "Default")
      (node (ref "HDR_B") (pin "5") (pinfunction "5_5") (pintype "passive"))
    )
    (net (code "289") (name "/SDA") (class "Default")
      (node (ref "HDR_B") (pin "3") (pinfunction "3_3") (pintype "passive"))
    )
    (net (code "290") (name "/SLEEP_N") (class "Default")
      (node (ref "HDR_T") (pin "93") (pinfunction "93_93") (pintype "passive+no_connect"))
    )
    (net (code "291") (name "/SPI_CLK") (class "Default")
      (node (ref "HDR_T") (pin "46") (pinfunction "46_46") (pintype "passive"))
    )
    (net (code "292") (name "/SPI_DIN") (class "Default")
      (node (ref "HDR_T") (pin "44") (pinfunction "44_44") (pintype "passive"))
    )
    (net (code "293") (name "/SPI_DOUT") (class "Default")
      (node (ref "HDR_T") (pin "50") (pinfunction "50_50") (pintype "passive"))
    )
    (net (code "294") (name "/SPI_MODE") (class "Default")
      (node (ref "HDR_T") (pin "52") (pinfunction "52_52") (pintype "passive"))
    )
    (net (code "295") (name "/SPI_SEL") (class "Default")
      (node (ref "HDR_T") (pin "48") (pinfunction "48_48") (pintype "passive"))
    )
    (net (code "296") (name "/SW0") (class "Default")
      (node (ref "HDR_B") (pin "42") (pinfunction "42_42") (pintype "passive"))
    )
    (net (code "297") (name "/SW1") (class "Default")
      (node (ref "HDR_B") (pin "44") (pinfunction "44_44") (pintype "passive"))
    )
    (net (code "298") (name "/SW2") (class "Default")
      (node (ref "HDR_B") (pin "46") (pinfunction "46_46") (pintype "passive"))
    )
    (net (code "299") (name "/SW3") (class "Default")
      (node (ref "HDR_B") (pin "48") (pinfunction "48_48") (pintype "passive"))
    )
    (net (code "300") (name "/SW4") (class "Default")
      (node (ref "HDR_B") (pin "50") (pinfunction "50_50") (pintype "passive"))
    )
    (net (code "303") (name "/USER_LED0") (class "Default")
      (node (ref "HDR_B") (pin "6") (pinfunction "6_6") (pintype "passive"))
    )
    (net (code "304") (name "/USER_LED1") (class "Default")
      (node (ref "HDR_B") (pin "8") (pinfunction "8_8") (pintype "passive"))
    )
    (net (code "305") (name "/USER_LED2") (class "Default")
      (node (ref "HDR_B") (pin "10") (pinfunction "10_10") (pintype "passive"))
    )
    (net (code "306") (name "/USER_LED3") (class "Default")
      (node (ref "HDR_B") (pin "12") (pinfunction "12_12") (pintype "passive"))
    )
    (net (code "307") (name "/USER_LED4") (class "Default")
      (node (ref "HDR_B") (pin "14") (pinfunction "14_14") (pintype "passive"))
    )
    (net (code "308") (name "/USER_LED5") (class "Default")
      (node (ref "HDR_B") (pin "16") (pinfunction "16_16") (pintype "passive"))
    )
    (net (code "309") (name "/USER_LED6") (class "Default")
      (node (ref "HDR_B") (pin "18") (pinfunction "18_18") (pintype "passive"))
    )
    (net (code "310") (name "/USER_LED7") (class "Default")
      (node (ref "HDR_B") (pin "20") (pinfunction "20_20") (pintype "passive"))
    )
    (net (code "327") (name "3V3") (class "Default")
      (node (ref "HDR_B") (pin "94") (pinfunction "94_94") (pintype "passive"))
      (node (ref "HDR_B") (pin "96") (pinfunction "96_96") (pintype "passive"))
      (node (ref "HDR_T") (pin "94") (pinfunction "94_94") (pintype "passive"))
      (node (ref "HDR_T") (pin "96") (pinfunction "96_96") (pintype "passive"))
      (node (ref "NT1") (pin "2") (pinfunction "Net2_2") (pintype "passive"))
    )
    (net (code "328") (name "5V0") (class "Default")
      (node (ref "HDR_B") (pin "97") (pinfunction "97_97") (pintype "passive"))
      (node (ref "HDR_B") (pin "99") (pinfunction "99_99") (pintype "passive"))
      (node (ref "HDR_T") (pin "97") (pinfunction "97_97") (pintype "passive"))
      (node (ref "HDR_T") (pin "99") (pinfunction "99_99") (pintype "passive"))
    )
    (net (code "329") (name "GND") (class "Default")
      (node (ref "HDR_B") (pin "1") (pinfunction "1_1") (pintype "passive"))
      (node (ref "HDR_B") (pin "100") (pinfunction "100_100") (pintype "passive"))
      (node (ref "HDR_B") (pin "98") (pinfunction "98_98") (pintype "passive"))
      (node (ref "HDR_B") (pin "MH1") (pinfunction "MH1_MH1") (pintype "passive"))
      (node (ref "HDR_B") (pin "MH2") (pinfunction "MH2_MH2") (pintype "passive"))
      (node (ref "HDR_B") (pin "MH3") (pinfunction "MH3_MH3") (pintype "passive"))
      (node (ref "HDR_B") (pin "MH4") (pinfunction "MH4_MH4") (pintype "passive"))
      (node (ref "HDR_L") (pin "MH1") (pinfunction "MH1_MH1") (pintype "passive"))
      (node (ref "HDR_L") (pin "MH2") (pinfunction "MH2_MH2") (pintype "passive"))
      (node (ref "HDR_L") (pin "MH3") (pinfunction "MH3_MH3") (pintype "passive"))
      (node (ref "HDR_L") (pin "MH4") (pinfunction "MH4_MH4") (pintype "passive"))
      (node (ref "HDR_T") (pin "1") (pinfunction "1_1") (pintype "passive"))
      (node (ref "HDR_T") (pin "100") (pinfunction "100_100") (pintype "passive"))
      (node (ref "HDR_T") (pin "98") (pinfunction "98_98") (pintype "passive"))
      (node (ref "HDR_T") (pin "MH1") (pinfunction "MH1_MH1") (pintype "passive"))
      (node (ref "HDR_T") (pin "MH2") (pinfunction "MH2_MH2") (pintype "passive"))
      (node (ref "HDR_T") (pin "MH3") (pinfunction "MH3_MH3") (pintype "passive"))
      (node (ref "HDR_T") (pin "MH4") (pinfunction "MH4_MH4") (pintype "passive"))
    )
    (net (code "330") (name "unconnected-(HDR_B-Pad93)") (class "Default")
      (node (ref "HDR_B") (pin "93") (pinfunction "93_93") (pintype "passive+no_connect"))
    )
    (net (code "331") (name "unconnected-(HDR_B-Pad95)") (class "Default")
      (node (ref "HDR_B") (pin "95") (pinfunction "95_95") (pintype "passive+no_connect"))
    )
    (net (code "332") (name "unconnected-(HDR_T-Pad95)") (class "Default")
      (node (ref "HDR_T") (pin "95") (pinfunction "95_95") (pintype "passive+no_connect"))
    )
  )
)
